# LED_Sign_Board.net
KiCad netlist of a schematic drawn in EAGLE
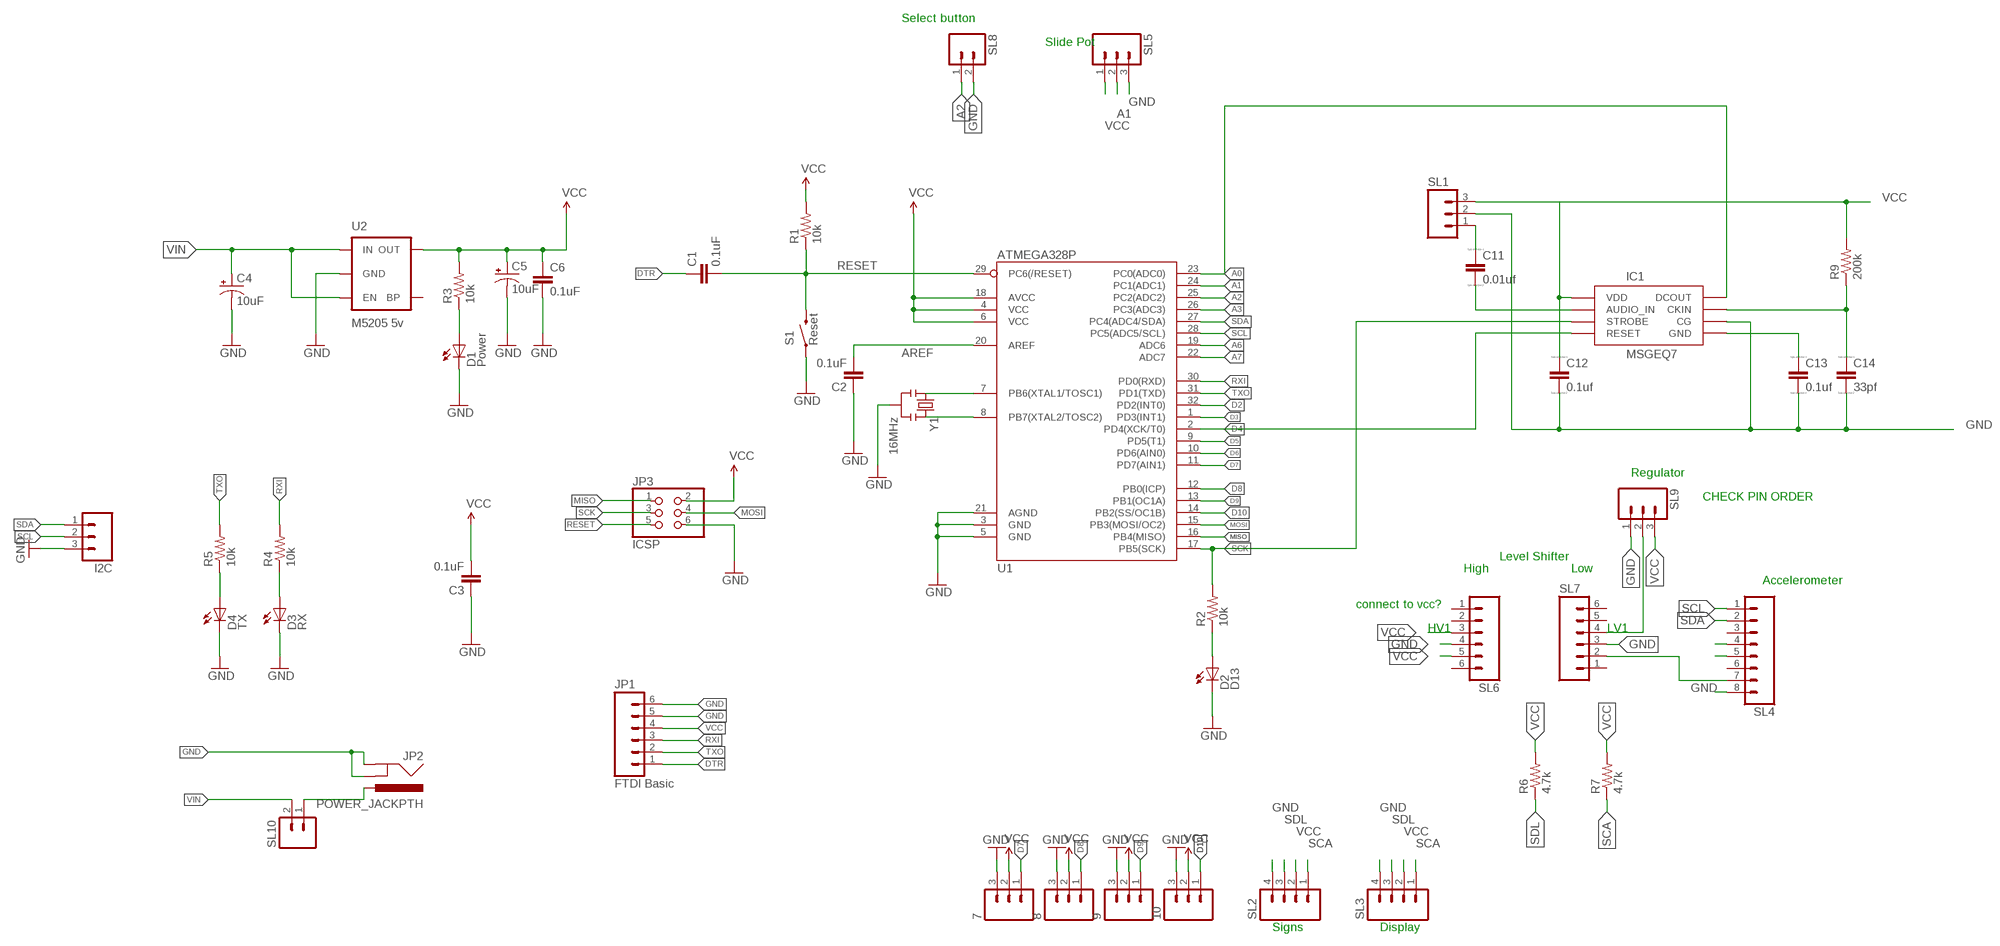
[diagram p0: schematic, sheet 1]

(export (version "E")
  (design (tool "Eeschema 10.0.6"))
  (components
    (comp (ref "7")
      (value "M03PTH")
      (footprint "eagle-import:1X03")
      (libsource (lib "eagle-import") (part "M03PTH"))
    )
    (comp (ref "8")
      (value "M03PTH")
      (footprint "eagle-import:1X03")
      (libsource (lib "eagle-import") (part "M03PTH"))
    )
    (comp (ref "9")
      (value "M03PTH")
      (footprint "eagle-import:1X03")
      (libsource (lib "eagle-import") (part "M03PTH"))
    )
    (comp (ref "10")
      (value "M03PTH")
      (footprint "eagle-import:1X03")
      (libsource (lib "eagle-import") (part "M03PTH"))
    )
    (comp (ref "C1")
      (value "0.1uF")
      (footprint "eagle-import:0603-CAP")
      (libsource (lib "eagle-import") (part "CAP0603-CAP"))
    )
    (comp (ref "C2")
      (value "0.1uF")
      (footprint "eagle-import:0603-CAP")
      (libsource (lib "eagle-import") (part "CAP0603-CAP"))
    )
    (comp (ref "C3")
      (value "0.1uF")
      (footprint "eagle-import:0603-CAP")
      (libsource (lib "eagle-import") (part "CAP0603-CAP"))
    )
    (comp (ref "C4")
      (value "10uF")
      (footprint "eagle-import:EIA3216")
      (libsource (lib "eagle-import") (part "CAP_POL1206"))
    )
    (comp (ref "C5")
      (value "10uF")
      (footprint "eagle-import:EIA3216")
      (libsource (lib "eagle-import") (part "CAP_POL1206"))
    )
    (comp (ref "C6")
      (value "0.1uF")
      (footprint "eagle-import:0603-CAP")
      (libsource (lib "eagle-import") (part "CAP0603-CAP"))
    )
    (comp (ref "C11")
      (value "0.01uf")
      (footprint "eagle-import:C0201")
      (libsource (lib "eagle-import") (part "CC0201"))
    )
    (comp (ref "C12")
      (value "0.1uf")
      (footprint "eagle-import:C0201")
      (libsource (lib "eagle-import") (part "CC0201"))
    )
    (comp (ref "C13")
      (value "0.1uf")
      (footprint "eagle-import:C0201")
      (libsource (lib "eagle-import") (part "CC0201"))
    )
    (comp (ref "C14")
      (value "33pf")
      (footprint "eagle-import:C0201")
      (libsource (lib "eagle-import") (part "CC0201"))
    )
    (comp (ref "D1")
      (value "Power")
      (footprint "eagle-import:LED-0603")
      (libsource (lib "eagle-import") (part "LED-RED0603"))
    )
    (comp (ref "D2")
      (value "D13")
      (footprint "eagle-import:LED-0603")
      (libsource (lib "eagle-import") (part "LED-RED0603"))
    )
    (comp (ref "D3")
      (value "RX")
      (footprint "eagle-import:LED-0603")
      (libsource (lib "eagle-import") (part "LED-GREEN0603"))
    )
    (comp (ref "D4")
      (value "TX")
      (footprint "eagle-import:LED-0603")
      (libsource (lib "eagle-import") (part "LED-RED0603"))
    )
    (comp (ref "I2C")
      (value "M03PTH")
      (footprint "eagle-import:1X03")
      (libsource (lib "eagle-import") (part "M03PTH"))
    )
    (comp (ref "IC1")
      (value "MSGEQ7DIL")
      (footprint "eagle-import:DIL-08")
      (libsource (lib "eagle-import") (part "MSGEQ7DIL"))
    )
    (comp (ref "JP1")
      (value "FTDI Basic")
      (footprint "eagle-import:1X06")
      (libsource (lib "eagle-import") (part "M06SIP"))
    )
    (comp (ref "JP2")
      (value "POWER_JACKPTH")
      (footprint "eagle-import:POWER_JACK_PTH")
      (libsource (lib "eagle-import") (part "POWER_JACKPTH"))
    )
    (comp (ref "JP3")
      (value "ICSP")
      (footprint "eagle-import:2X03")
      (libsource (lib "eagle-import") (part "PINHD-2X3"))
    )
    (comp (ref "R1")
      (value "10k")
      (footprint "eagle-import:0603-RES")
      (libsource (lib "eagle-import") (part "RESISTOR0603-RES"))
    )
    (comp (ref "R2")
      (value "10k")
      (footprint "eagle-import:0603-RES")
      (libsource (lib "eagle-import") (part "RESISTOR0603-RES"))
    )
    (comp (ref "R3")
      (value "10k")
      (footprint "eagle-import:0603-RES")
      (libsource (lib "eagle-import") (part "RESISTOR0603-RES"))
    )
    (comp (ref "R4")
      (value "10k")
      (footprint "eagle-import:0603-RES")
      (libsource (lib "eagle-import") (part "RESISTOR0603-RES"))
    )
    (comp (ref "R5")
      (value "10k")
      (footprint "eagle-import:0603-RES")
      (libsource (lib "eagle-import") (part "RESISTOR0603-RES"))
    )
    (comp (ref "R6")
      (value "4.7k")
      (footprint "eagle-import:1206")
      (libsource (lib "eagle-import") (part "SparkFun-Resistors_RESISTOR1206"))
    )
    (comp (ref "R7")
      (value "4.7k")
      (footprint "eagle-import:1206")
      (libsource (lib "eagle-import") (part "SparkFun-Resistors_RESISTOR1206"))
    )
    (comp (ref "R9")
      (value "200k")
      (footprint "eagle-import:1206")
      (libsource (lib "eagle-import") (part "SparkFun-Resistors_RESISTOR1206"))
    )
    (comp (ref "S1")
      (value "Reset")
      (footprint "eagle-import:TACTILE_SWITCH_SMD")
      (libsource (lib "eagle-import") (part "SWITCH-MOMENTARY-2SMD"))
    )
    (comp (ref "SL1")
      (value "M03")
      (footprint "eagle-import:03P")
      (libsource (lib "eagle-import") (part "M03"))
    )
    (comp (ref "SL2")
      (value "M04")
      (footprint "eagle-import:04P")
      (libsource (lib "eagle-import") (part "M04"))
    )
    (comp (ref "SL3")
      (value "M04")
      (footprint "eagle-import:04P")
      (libsource (lib "eagle-import") (part "M04"))
    )
    (comp (ref "SL4")
      (value "M08")
      (footprint "eagle-import:08P")
      (libsource (lib "eagle-import") (part "M08"))
    )
    (comp (ref "SL5")
      (value "M03")
      (footprint "eagle-import:03P")
      (libsource (lib "eagle-import") (part "M03"))
    )
    (comp (ref "SL6")
      (value "M06")
      (footprint "eagle-import:06P")
      (libsource (lib "eagle-import") (part "M06"))
    )
    (comp (ref "SL7")
      (value "M06")
      (footprint "eagle-import:06P")
      (libsource (lib "eagle-import") (part "M06"))
    )
    (comp (ref "SL8")
      (value "M02")
      (footprint "eagle-import:02P")
      (libsource (lib "eagle-import") (part "M02"))
    )
    (comp (ref "SL9")
      (value "M03")
      (footprint "eagle-import:03P")
      (libsource (lib "eagle-import") (part "M03"))
    )
    (comp (ref "SL10")
      (value "M02")
      (footprint "eagle-import:02P")
      (libsource (lib "eagle-import") (part "M02"))
    )
    (comp (ref "U1")
      (value "ATMEGA328P")
      (footprint "eagle-import:TQFP32-08")
      (libsource (lib "eagle-import") (part "ATMEGA328_SMT"))
    )
    (comp (ref "U2")
      (value "M5205 5v")
      (footprint "eagle-import:SOT23-5")
      (libsource (lib "eagle-import") (part "MIC52055V"))
    )
    (comp (ref "Y1")
      (value "16MHz")
      (footprint "eagle-import:RESONATOR-SMD")
      (libsource (lib "eagle-import") (part "RESONATOR16MHZ"))
    )
  )
  (nets
    (net (code "1") (name "/AREF") (class "Default")
      (node (ref "C2") (pin "2") (pinfunction "2_2") (pintype "passive"))
      (node (ref "U1") (pin "20") (pinfunction "AREF_20") (pintype "bidirectional"))
    )
    (net (code "2") (name "A0") (class "Default")
      (node (ref "IC1") (pin "3") (pinfunction "DCOUT_3") (pintype "bidirectional"))
      (node (ref "U1") (pin "23") (pinfunction "PC0(ADC0)_23") (pintype "bidirectional"))
    )
    (net (code "3") (name "A1") (class "Default")
      (node (ref "SL5") (pin "2") (pinfunction "2_2") (pintype "passive"))
      (node (ref "U1") (pin "24") (pinfunction "PC1(ADC1)_24") (pintype "bidirectional"))
    )
    (net (code "4") (name "A2") (class "Default")
      (node (ref "SL8") (pin "1") (pinfunction "1_1") (pintype "passive"))
      (node (ref "U1") (pin "25") (pinfunction "PC2(ADC2)_25") (pintype "bidirectional"))
    )
    (net (code "5") (name "A3") (class "Default")
      (node (ref "U1") (pin "26") (pinfunction "PC3(ADC3)_26") (pintype "bidirectional"))
    )
    (net (code "6") (name "A6") (class "Default")
      (node (ref "U1") (pin "19") (pinfunction "ADC6_19") (pintype "bidirectional"))
    )
    (net (code "7") (name "A7") (class "Default")
      (node (ref "U1") (pin "22") (pinfunction "ADC7_22") (pintype "bidirectional"))
    )
    (net (code "8") (name "D2") (class "Default")
      (node (ref "U1") (pin "32") (pinfunction "PD2(INT0)_32") (pintype "bidirectional"))
    )
    (net (code "9") (name "D3") (class "Default")
      (node (ref "U1") (pin "1") (pinfunction "PD3(INT1)_1") (pintype "bidirectional"))
    )
    (net (code "10") (name "D4") (class "Default")
      (node (ref "IC1") (pin "7") (pinfunction "RESET_7") (pintype "input"))
      (node (ref "U1") (pin "2") (pinfunction "PD4(XCK/T0)_2") (pintype "bidirectional"))
    )
    (net (code "11") (name "D5") (class "Default")
      (node (ref "U1") (pin "9") (pinfunction "PD5(T1)_9") (pintype "bidirectional"))
    )
    (net (code "12") (name "D6") (class "Default")
      (node (ref "U1") (pin "10") (pinfunction "PD6(AIN0)_10") (pintype "bidirectional"))
    )
    (net (code "13") (name "D7") (class "Default")
      (node (ref "7") (pin "1") (pinfunction "1_1") (pintype "passive"))
      (node (ref "U1") (pin "11") (pinfunction "PD7(AIN1)_11") (pintype "bidirectional"))
    )
    (net (code "14") (name "D8") (class "Default")
      (node (ref "8") (pin "1") (pinfunction "1_1") (pintype "passive"))
      (node (ref "U1") (pin "12") (pinfunction "PB0(ICP)_12") (pintype "bidirectional"))
    )
    (net (code "15") (name "D9") (class "Default")
      (node (ref "9") (pin "1") (pinfunction "1_1") (pintype "passive"))
      (node (ref "U1") (pin "13") (pinfunction "PB1(OC1A)_13") (pintype "bidirectional"))
    )
    (net (code "16") (name "D10") (class "Default")
      (node (ref "10") (pin "1") (pinfunction "1_1") (pintype "passive"))
      (node (ref "U1") (pin "14") (pinfunction "PB2(SS/OC1B)_14") (pintype "bidirectional"))
    )
    (net (code "17") (name "DTR") (class "Default")
      (node (ref "C1") (pin "1") (pinfunction "1_1") (pintype "passive"))
      (node (ref "JP1") (pin "1") (pinfunction "1_1") (pintype "passive"))
    )
    (net (code "18") (name "GND") (class "Default")
      (node (ref "10") (pin "3") (pinfunction "3_3") (pintype "passive"))
      (node (ref "7") (pin "3") (pinfunction "3_3") (pintype "passive"))
      (node (ref "8") (pin "3") (pinfunction "3_3") (pintype "passive"))
      (node (ref "9") (pin "3") (pinfunction "3_3") (pintype "passive"))
      (node (ref "C12") (pin "2") (pinfunction "2_2") (pintype "passive"))
      (node (ref "C13") (pin "2") (pinfunction "2_2") (pintype "passive"))
      (node (ref "C14") (pin "2") (pinfunction "2_2") (pintype "passive"))
      (node (ref "C2") (pin "1") (pinfunction "1_1") (pintype "passive"))
      (node (ref "C3") (pin "1") (pinfunction "1_1") (pintype "passive"))
      (node (ref "C4") (pin "C") (pinfunction "-_C") (pintype "passive"))
      (node (ref "C5") (pin "C") (pinfunction "-_C") (pintype "passive"))
      (node (ref "C6") (pin "2") (pinfunction "2_2") (pintype "passive"))
      (node (ref "D1") (pin "C") (pinfunction "C_C") (pintype "passive"))
      (node (ref "D2") (pin "C") (pinfunction "C_C") (pintype "passive"))
      (node (ref "D3") (pin "C") (pinfunction "C_C") (pintype "passive"))
      (node (ref "D4") (pin "C") (pinfunction "C_C") (pintype "passive"))
      (node (ref "I2C") (pin "3") (pinfunction "3_3") (pintype "passive"))
      (node (ref "IC1") (pin "6") (pinfunction "CG_6") (pintype "bidirectional"))
      (node (ref "JP1") (pin "5") (pinfunction "5_5") (pintype "passive"))
      (node (ref "JP1") (pin "6") (pinfunction "6_6") (pintype "passive"))
      (node (ref "JP2") (pin "GND") (pinfunction "GND_GND") (pintype "bidirectional"))
      (node (ref "JP2") (pin "GNDBREAK") (pinfunction "GNDBREAK_GNDBREAK") (pintype "bidirectional"))
      (node (ref "JP3") (pin "6") (pinfunction "6_6") (pintype "passive"))
      (node (ref "S1") (pin "1") (pinfunction "1_1") (pintype "passive"))
      (node (ref "SL1") (pin "2") (pinfunction "2_2") (pintype "passive"))
      (node (ref "SL2") (pin "4") (pinfunction "4_4") (pintype "passive"))
      (node (ref "SL3") (pin "4") (pinfunction "4_4") (pintype "passive"))
      (node (ref "SL4") (pin "8") (pinfunction "8_8") (pintype "passive"))
      (node (ref "SL5") (pin "3") (pinfunction "3_3") (pintype "passive"))
      (node (ref "SL6") (pin "4") (pinfunction "4_4") (pintype "passive"))
      (node (ref "SL7") (pin "3") (pinfunction "3_3") (pintype "passive"))
      (node (ref "SL7") (pin "4") (pinfunction "4_4") (pintype "passive"))
      (node (ref "SL8") (pin "2") (pinfunction "2_2") (pintype "passive"))
      (node (ref "SL9") (pin "1") (pinfunction "1_1") (pintype "passive"))
      (node (ref "SL9") (pin "2") (pinfunction "2_2") (pintype "passive"))
      (node (ref "U1") (pin "21") (pinfunction "AGND_21") (pintype "bidirectional"))
      (node (ref "U1") (pin "3") (pinfunction "GND_3") (pintype "bidirectional"))
      (node (ref "U1") (pin "5") (pinfunction "GND_5") (pintype "bidirectional"))
      (node (ref "U2") (pin "2") (pinfunction "GND_2") (pintype "input"))
      (node (ref "Y1") (pin "2") (pinfunction "2_2") (pintype "passive"))
    )
    (net (code "19") (name "MISO") (class "Default")
      (node (ref "JP3") (pin "1") (pinfunction "1_1") (pintype "passive"))
      (node (ref "U1") (pin "16") (pinfunction "PB4(MISO)_16") (pintype "bidirectional"))
    )
    (net (code "20") (name "MOSI") (class "Default")
      (node (ref "JP3") (pin "4") (pinfunction "4_4") (pintype "passive"))
      (node (ref "U1") (pin "15") (pinfunction "PB3(MOSI/OC2)_15") (pintype "bidirectional"))
    )
    (net (code "21") (name "Net-(C11-Pad1)") (class "Default")
      (node (ref "C11") (pin "1") (pinfunction "1_1") (pintype "passive"))
      (node (ref "SL1") (pin "1") (pinfunction "1_1") (pintype "passive"))
    )
    (net (code "22") (name "Net-(D1-PadA)") (class "Default")
      (node (ref "D1") (pin "A") (pinfunction "A_A") (pintype "passive"))
      (node (ref "R3") (pin "1") (pinfunction "1_1") (pintype "passive"))
    )
    (net (code "23") (name "Net-(D2-PadA)") (class "Default")
      (node (ref "D2") (pin "A") (pinfunction "A_A") (pintype "passive"))
      (node (ref "R2") (pin "1") (pinfunction "1_1") (pintype "passive"))
    )
    (net (code "24") (name "Net-(D3-PadA)") (class "Default")
      (node (ref "D3") (pin "A") (pinfunction "A_A") (pintype "passive"))
      (node (ref "R4") (pin "1") (pinfunction "1_1") (pintype "passive"))
    )
    (net (code "25") (name "Net-(D4-PadA)") (class "Default")
      (node (ref "D4") (pin "A") (pinfunction "A_A") (pintype "passive"))
      (node (ref "R5") (pin "1") (pinfunction "1_1") (pintype "passive"))
    )
    (net (code "26") (name "Net-(IC1-AUDIO_IN)") (class "Default")
      (node (ref "C11") (pin "2") (pinfunction "2_2") (pintype "passive"))
      (node (ref "IC1") (pin "5") (pinfunction "AUDIO_IN_5") (pintype "input"))
    )
    (net (code "27") (name "Net-(IC1-CKIN)") (class "Default")
      (node (ref "C14") (pin "1") (pinfunction "1_1") (pintype "passive"))
      (node (ref "IC1") (pin "8") (pinfunction "CKIN_8") (pintype "bidirectional"))
      (node (ref "R9") (pin "1") (pinfunction "1_1") (pintype "passive"))
    )
    (net (code "28") (name "Net-(IC1-GND)") (class "Default")
      (node (ref "C13") (pin "1") (pinfunction "1_1") (pintype "passive"))
      (node (ref "IC1") (pin "2") (pinfunction "GND_2") (pintype "bidirectional"))
    )
    (net (code "29") (name "Net-(JP2-PadPWR)") (class "Default")
      (node (ref "JP2") (pin "PWR") (pinfunction "PWR_PWR") (pintype "bidirectional"))
      (node (ref "SL10") (pin "1") (pinfunction "1_1") (pintype "passive"))
    )
    (net (code "30") (name "Net-(SL4-Pad7)") (class "Default")
      (node (ref "SL4") (pin "7") (pinfunction "7_7") (pintype "passive"))
      (node (ref "SL7") (pin "2") (pinfunction "2_2") (pintype "passive"))
    )
    (net (code "31") (name "Net-(U1-PB6(XTAL1{slash}TOSC1))") (class "Default")
      (node (ref "U1") (pin "7") (pinfunction "PB6(XTAL1/TOSC1)_7") (pintype "bidirectional"))
      (node (ref "Y1") (pin "1") (pinfunction "1_1") (pintype "passive"))
    )
    (net (code "32") (name "Net-(U1-PB7(XTAL2{slash}TOSC2))") (class "Default")
      (node (ref "U1") (pin "8") (pinfunction "PB7(XTAL2/TOSC2)_8") (pintype "bidirectional"))
      (node (ref "Y1") (pin "3") (pinfunction "3_3") (pintype "passive"))
    )
    (net (code "33") (name "RESET") (class "Default")
      (node (ref "C1") (pin "2") (pinfunction "2_2") (pintype "passive"))
      (node (ref "JP3") (pin "5") (pinfunction "5_5") (pintype "passive"))
      (node (ref "R1") (pin "1") (pinfunction "1_1") (pintype "passive"))
      (node (ref "S1") (pin "3") (pinfunction "2_3") (pintype "passive"))
      (node (ref "U1") (pin "29") (pinfunction "PC6(/RESET)_29") (pintype "bidirectional"))
    )
    (net (code "34") (name "RXI") (class "Default")
      (node (ref "JP1") (pin "3") (pinfunction "3_3") (pintype "passive"))
      (node (ref "R4") (pin "2") (pinfunction "2_2") (pintype "passive"))
      (node (ref "U1") (pin "30") (pinfunction "PD0(RXD)_30") (pintype "bidirectional"))
    )
    (net (code "35") (name "SCA") (class "Default")
      (node (ref "R7") (pin "1") (pinfunction "1_1") (pintype "passive"))
      (node (ref "SL2") (pin "1") (pinfunction "1_1") (pintype "passive"))
      (node (ref "SL3") (pin "1") (pinfunction "1_1") (pintype "passive"))
    )
    (net (code "36") (name "SCK") (class "Default")
      (node (ref "IC1") (pin "4") (pinfunction "STROBE_4") (pintype "input"))
      (node (ref "JP3") (pin "3") (pinfunction "3_3") (pintype "passive"))
      (node (ref "R2") (pin "2") (pinfunction "2_2") (pintype "passive"))
      (node (ref "U1") (pin "17") (pinfunction "PB5(SCK)_17") (pintype "bidirectional"))
    )
    (net (code "37") (name "SCL") (class "Default")
      (node (ref "I2C") (pin "2") (pinfunction "2_2") (pintype "passive"))
      (node (ref "SL4") (pin "1") (pinfunction "1_1") (pintype "passive"))
      (node (ref "U1") (pin "28") (pinfunction "PC5(ADC5/SCL)_28") (pintype "bidirectional"))
    )
    (net (code "38") (name "SDA") (class "Default")
      (node (ref "I2C") (pin "1") (pinfunction "1_1") (pintype "passive"))
      (node (ref "SL4") (pin "2") (pinfunction "2_2") (pintype "passive"))
      (node (ref "U1") (pin "27") (pinfunction "PC4(ADC4/SDA)_27") (pintype "bidirectional"))
    )
    (net (code "39") (name "SDL") (class "Default")
      (node (ref "R6") (pin "1") (pinfunction "1_1") (pintype "passive"))
      (node (ref "SL2") (pin "3") (pinfunction "3_3") (pintype "passive"))
      (node (ref "SL3") (pin "3") (pinfunction "3_3") (pintype "passive"))
    )
    (net (code "40") (name "TXO") (class "Default")
      (node (ref "JP1") (pin "2") (pinfunction "2_2") (pintype "passive"))
      (node (ref "R5") (pin "2") (pinfunction "2_2") (pintype "passive"))
      (node (ref "U1") (pin "31") (pinfunction "PD1(TXD)_31") (pintype "bidirectional"))
    )
    (net (code "41") (name "VCC") (class "Default")
      (node (ref "10") (pin "2") (pinfunction "2_2") (pintype "passive"))
      (node (ref "7") (pin "2") (pinfunction "2_2") (pintype "passive"))
      (node (ref "8") (pin "2") (pinfunction "2_2") (pintype "passive"))
      (node (ref "9") (pin "2") (pinfunction "2_2") (pintype "passive"))
      (node (ref "C12") (pin "1") (pinfunction "1_1") (pintype "passive"))
      (node (ref "C3") (pin "2") (pinfunction "2_2") (pintype "passive"))
      (node (ref "C5") (pin "A") (pinfunction "+_A") (pintype "passive"))
      (node (ref "C6") (pin "1") (pinfunction "1_1") (pintype "passive"))
      (node (ref "IC1") (pin "1") (pinfunction "VDD_1") (pintype "input"))
      (node (ref "JP1") (pin "4") (pinfunction "4_4") (pintype "passive"))
      (node (ref "JP3") (pin "2") (pinfunction "2_2") (pintype "passive"))
      (node (ref "R1") (pin "2") (pinfunction "2_2") (pintype "passive"))
      (node (ref "R3") (pin "2") (pinfunction "2_2") (pintype "passive"))
      (node (ref "R6") (pin "2") (pinfunction "2_2") (pintype "passive"))
      (node (ref "R7") (pin "2") (pinfunction "2_2") (pintype "passive"))
      (node (ref "R9") (pin "2") (pinfunction "2_2") (pintype "passive"))
      (node (ref "SL1") (pin "3") (pinfunction "3_3") (pintype "passive"))
      (node (ref "SL2") (pin "2") (pinfunction "2_2") (pintype "passive"))
      (node (ref "SL3") (pin "2") (pinfunction "2_2") (pintype "passive"))
      (node (ref "SL5") (pin "1") (pinfunction "1_1") (pintype "passive"))
      (node (ref "SL6") (pin "3") (pinfunction "3_3") (pintype "passive"))
      (node (ref "SL6") (pin "5") (pinfunction "5_5") (pintype "passive"))
      (node (ref "SL9") (pin "3") (pinfunction "3_3") (pintype "passive"))
      (node (ref "U1") (pin "18") (pinfunction "AVCC_18") (pintype "bidirectional"))
      (node (ref "U1") (pin "4") (pinfunction "VCC_4") (pintype "bidirectional"))
      (node (ref "U1") (pin "6") (pinfunction "VCC_6") (pintype "bidirectional"))
      (node (ref "U2") (pin "5") (pinfunction "OUT_5") (pintype "passive"))
    )
    (net (code "42") (name "VIN") (class "Default")
      (node (ref "C4") (pin "A") (pinfunction "+_A") (pintype "passive"))
      (node (ref "SL10") (pin "2") (pinfunction "2_2") (pintype "passive"))
      (node (ref "U2") (pin "1") (pinfunction "IN_1") (pintype "input"))
      (node (ref "U2") (pin "3") (pinfunction "EN_3") (pintype "input"))
    )
    (net (code "43") (name "unconnected-(SL4-Pad3)") (class "Default")
      (node (ref "SL4") (pin "3") (pinfunction "3_3") (pintype "passive"))
    )
    (net (code "44") (name "unconnected-(SL4-Pad4)") (class "Default")
      (node (ref "SL4") (pin "4") (pinfunction "4_4") (pintype "passive"))
    )
    (net (code "45") (name "unconnected-(SL4-Pad5)") (class "Default")
      (node (ref "SL4") (pin "5") (pinfunction "5_5") (pintype "passive"))
    )
    (net (code "46") (name "unconnected-(SL4-Pad6)") (class "Default")
      (node (ref "SL4") (pin "6") (pinfunction "6_6") (pintype "passive"))
    )
    (net (code "47") (name "unconnected-(SL6-Pad1)") (class "Default")
      (node (ref "SL6") (pin "1") (pinfunction "1_1") (pintype "passive"))
    )
    (net (code "48") (name "unconnected-(SL6-Pad2)") (class "Default")
      (node (ref "SL6") (pin "2") (pinfunction "2_2") (pintype "passive"))
    )
    (net (code "49") (name "unconnected-(SL6-Pad6)") (class "Default")
      (node (ref "SL6") (pin "6") (pinfunction "6_6") (pintype "passive"))
    )
    (net (code "50") (name "unconnected-(SL7-Pad1)") (class "Default")
      (node (ref "SL7") (pin "1") (pinfunction "1_1") (pintype "passive"))
    )
    (net (code "51") (name "unconnected-(SL7-Pad5)") (class "Default")
      (node (ref "SL7") (pin "5") (pinfunction "5_5") (pintype "passive"))
    )
    (net (code "52") (name "unconnected-(SL7-Pad6)") (class "Default")
      (node (ref "SL7") (pin "6") (pinfunction "6_6") (pintype "passive"))
    )
    (net (code "53") (name "unconnected-(U2-BP-Pad4)") (class "Default")
      (node (ref "U2") (pin "4") (pinfunction "BP_4") (pintype "input"))
    )
  )
)
